# LMR50410.net
KiCad netlist of a schematic drawn in Altium Designer
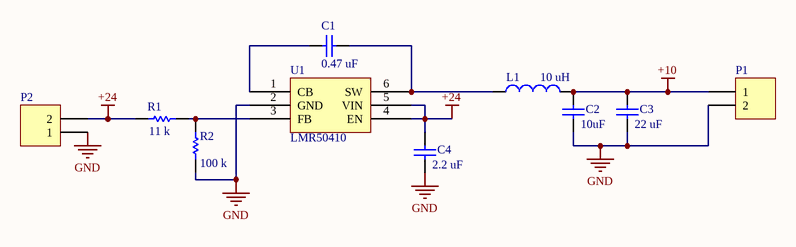
[diagram p0: LMR50410.SchDoc]

(export (version "E")
  (design (tool "Eeschema 10.0.6"))
  (components
    (comp (ref "C1")
      (value "0.47 uF")
      (footprint "0805 - Capacitor")
      (description "Nonpolarized Capacitor")
      (fields
        (field (name "MANUFACTURER") "Yageo")
        (field (name "MANUFACTURER PART NUMBER") "CC0805KKX5R8BB106")
      )
      (libsource (lib "General") (part "Capacitor - Nonpolarized"))
    )
    (comp (ref "C2")
      (value "10uF")
      (footprint "0805 - Capacitor")
      (description "Nonpolarized Capacitor")
      (fields
        (field (name "MANUFACTURER") "Yageo")
        (field (name "MANUFACTURER PART NUMBER") "CC0805KKX5R8BB106")
      )
      (libsource (lib "General") (part "Capacitor - Nonpolarized"))
    )
    (comp (ref "C3")
      (value "22 uF")
      (footprint "0805 - Capacitor")
      (description "Nonpolarized Capacitor")
      (fields
        (field (name "MANUFACTURER") "Yageo")
        (field (name "MANUFACTURER PART NUMBER") "CC0805KKX5R8BB106")
      )
      (libsource (lib "General") (part "Capacitor - Nonpolarized"))
    )
    (comp (ref "C4")
      (value "2.2 uF")
      (footprint "0805 - Capacitor")
      (description "Nonpolarized Capacitor")
      (fields
        (field (name "MANUFACTURER") "Yageo")
        (field (name "MANUFACTURER PART NUMBER") "CC0805KKX5R8BB106")
      )
      (libsource (lib "General") (part "Capacitor - Nonpolarized"))
    )
    (comp (ref "L1")
      (value "10 uH")
      (footprint "PA4340 - Inductor")
      (description "Inductor")
      (fields (field (name "MANUFACTURER PART NUMBER") "PA4340.103NLT") (field (name "MANUFACTURER") "Pulse"))
      (libsource (lib "General") (part "Inductor"))
    )
    (comp (ref "P1")
      (value "1x2 Header")
      (footprint "HDR1X2")
      (description "1x2 Pin Header")
      (libsource (lib "GeneralConnectors") (part "1x2 Header"))
    )
    (comp (ref "P2")
      (value "1x2 Header")
      (footprint "HDR1X2")
      (description "1x2 Pin Header")
      (libsource (lib "") (part "1x2 Header_1"))
    )
    (comp (ref "R1")
      (value "11 k")
      (footprint "0603 - Resistor")
      (description "Resistor")
      (fields (field (name "MANUFACTURER PART NUMBER") "ESR03EZPJ113") (field (name "MANUFACTURER") "ROHM"))
      (libsource (lib "General") (part "Resistor"))
    )
    (comp (ref "R2")
      (value "100 k")
      (footprint "0603 - Resistor")
      (description "Resistor")
      (fields (field (name "MANUFACTURER PART NUMBER") "ESR03EZPJ104") (field (name "MANUFACTURER") "ROHM"))
      (libsource (lib "General") (part "Resistor"))
    )
    (comp (ref "U1")
      (value "LMR50410")
      (footprint "LMR50410")
      (description "4V to 36V 1A, Buck Converter")
      (fields
        (field (name "MANUFACTURER") "Texas Instruments")
        (field (name "MANUFACTURER PART NUMBER") "LMR50410YQDBVRQ1")
      )
      (libsource (lib "GeneralComponents") (part "LMR50410"))
    )
  )
  (nets
    (net (code "1") (name "+10") (class "Default")
      (node (ref "C2") (pin "2") (pinfunction "2_2") (pintype "passive"))
      (node (ref "C3") (pin "2") (pinfunction "2_2") (pintype "passive"))
      (node (ref "L1") (pin "2") (pinfunction "2_2") (pintype "passive"))
      (node (ref "P1") (pin "1") (pinfunction "1_1") (pintype "passive"))
    )
    (net (code "2") (name "+24") (class "Default")
      (node (ref "C4") (pin "2") (pinfunction "2_2") (pintype "passive"))
      (node (ref "P2") (pin "2") (pinfunction "2_2") (pintype "passive"))
      (node (ref "R1") (pin "1") (pinfunction "1_1") (pintype "passive"))
      (node (ref "U1") (pin "4") (pinfunction "EN_4") (pintype "passive"))
      (node (ref "U1") (pin "5") (pinfunction "VIN_5") (pintype "power_in"))
    )
    (net (code "3") (name "GND") (class "Default")
      (node (ref "C2") (pin "1") (pinfunction "1_1") (pintype "passive"))
      (node (ref "C3") (pin "1") (pinfunction "1_1") (pintype "passive"))
      (node (ref "C4") (pin "1") (pinfunction "1_1") (pintype "passive"))
      (node (ref "P1") (pin "2") (pinfunction "2_2") (pintype "passive"))
      (node (ref "P2") (pin "1") (pinfunction "1_1") (pintype "passive"))
      (node (ref "R2") (pin "1") (pinfunction "1_1") (pintype "passive"))
      (node (ref "U1") (pin "2") (pinfunction "GND_2") (pintype "power_in"))
    )
    (net (code "4") (name "Net-(U1-CB)") (class "Default")
      (node (ref "C1") (pin "2") (pinfunction "2_2") (pintype "passive"))
      (node (ref "U1") (pin "1") (pinfunction "CB_1") (pintype "passive"))
    )
    (net (code "5") (name "Net-(U1-FB)") (class "Default")
      (node (ref "R1") (pin "2") (pinfunction "2_2") (pintype "passive"))
      (node (ref "R2") (pin "2") (pinfunction "2_2") (pintype "passive"))
      (node (ref "U1") (pin "3") (pinfunction "FB_3") (pintype "passive"))
    )
    (net (code "6") (name "Net-(U1-SW)") (class "Default")
      (node (ref "C1") (pin "1") (pinfunction "1_1") (pintype "passive"))
      (node (ref "L1") (pin "1") (pinfunction "1_1") (pintype "passive"))
      (node (ref "U1") (pin "6") (pinfunction "SW_6") (pintype "passive"))
    )
  )
)
